# 2017_CARTE_MOFSET.net
KiCad netlist of a schematic drawn in Altium Designer
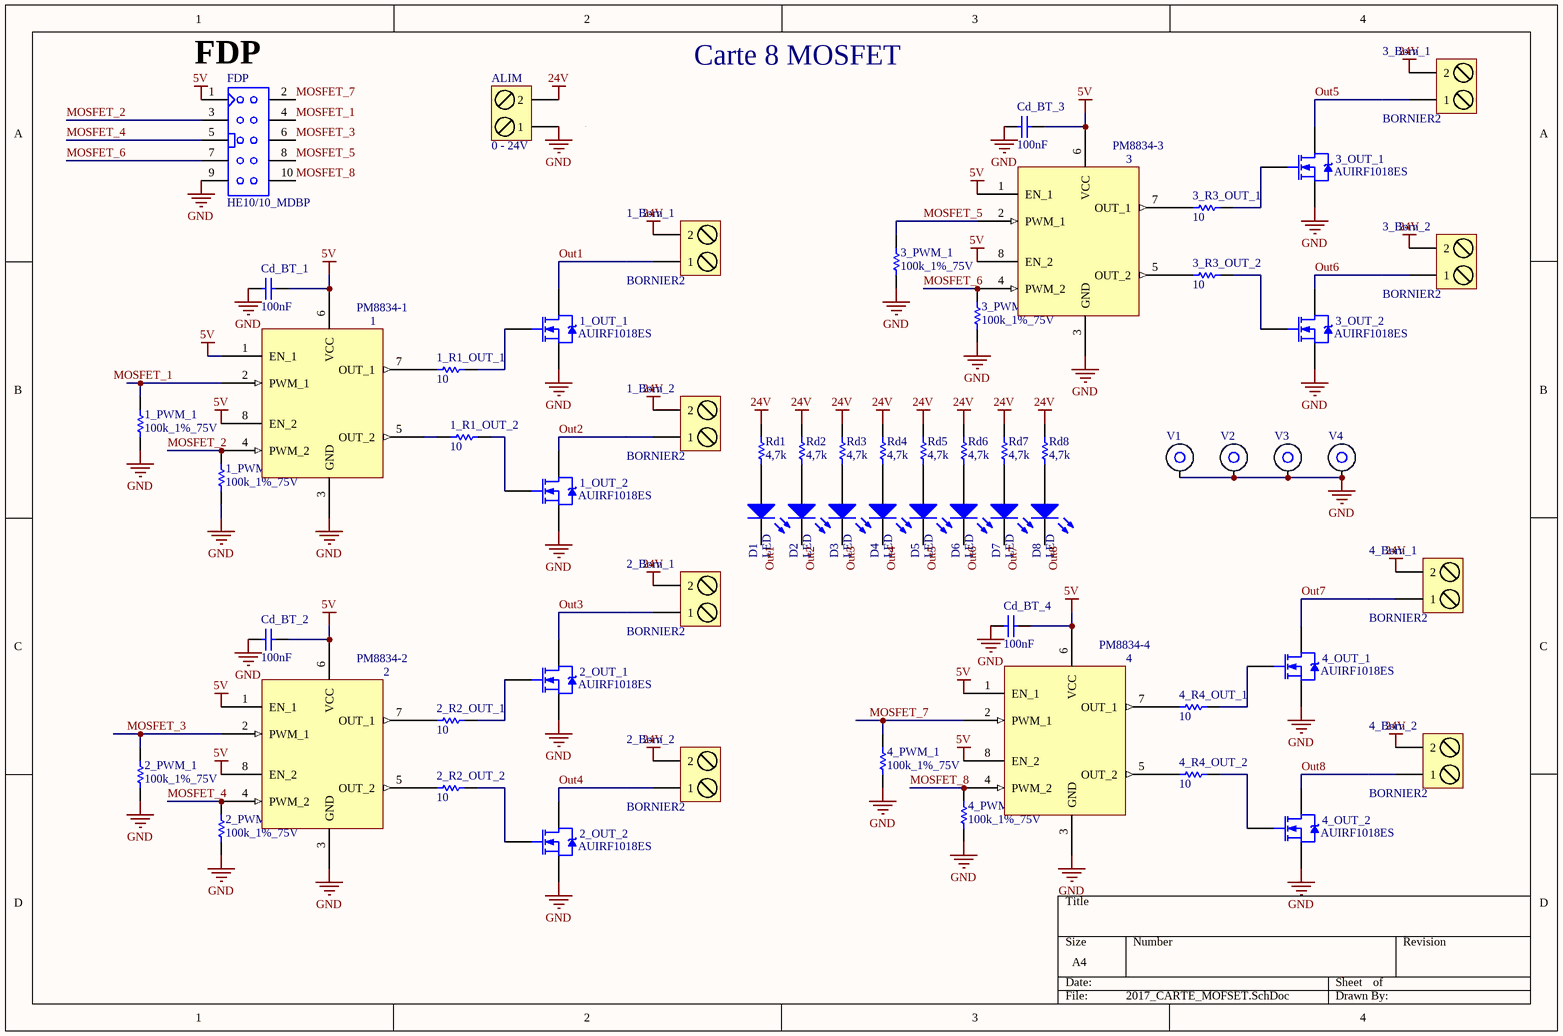
[diagram p0: 2017_CARTE_MOFSET.SchDoc]

(export (version "E")
  (design (tool "Eeschema 10.0.6"))
  (components
    (comp (ref "1")
      (value "PM8834-1")
      (footprint "SO8_N")
      (description "4 A dual low-side MOSFET driver")
      (libsource (lib "_ROBOT") (part "PM8834"))
    )
    (comp (ref "1_Born_1")
      (value "BORNIER2")
      (footprint "BORNIER2")
      (description "Terminal blocks, 2 pins, pitch=5mm")
      (libsource (lib "Connecteur") (part "BORNIER2"))
    )
    (comp (ref "1_Born_2")
      (value "BORNIER2")
      (footprint "BORNIER2")
      (description "Terminal blocks, 2 pins, pitch=5mm")
      (libsource (lib "Connecteur") (part "BORNIER2"))
    )
    (comp (ref "1_OUT_1")
      (value "AUIRF1018ES")
      (footprint "D2PAK_GROS_PAD")
      (description "HEXFET N-Channel Power MOSFET")
      (fields (field (name "PUBLISHER") "Altium Limited"))
      (libsource (lib "IR Discrete MOSFET - Power") (part "IRF1010S"))
    )
    (comp (ref "1_OUT_2")
      (value "AUIRF1018ES")
      (footprint "D2PAK_GROS_PAD")
      (description "HEXFET N-Channel Power MOSFET")
      (fields (field (name "PUBLISHER") "Altium Limited"))
      (libsource (lib "IR Discrete MOSFET - Power") (part "IRF1010S"))
    )
    (comp (ref "1_PWM_1")
      (value "100k_1%_75V")
      (footprint "R1206_N")
      (description "Resistor")
      (fields (field (name "PUBLISHER") "Altium Limited"))
      (libsource (lib "DG_Resistance") (part "Resistor"))
    )
    (comp (ref "1_PWM_2")
      (value "100k_1%_75V")
      (footprint "R1206_N")
      (description "Resistor")
      (fields (field (name "PUBLISHER") "Altium Limited"))
      (libsource (lib "DG_Resistance") (part "Resistor"))
    )
    (comp (ref "1_R1_OUT_1")
      (value "10")
      (footprint "R1206_N")
      (description "Resistor")
      (fields (field (name "PUBLISHER") "Altium Limited"))
      (libsource (lib "_ROBOT") (part "Resistor"))
    )
    (comp (ref "1_R1_OUT_2")
      (value "10")
      (footprint "R1206_N")
      (description "Resistor")
      (fields (field (name "PUBLISHER") "Altium Limited"))
      (libsource (lib "_ROBOT") (part "Resistor"))
    )
    (comp (ref "2")
      (value "PM8834-2")
      (footprint "SO8_N")
      (description "4 A dual low-side MOSFET driver")
      (libsource (lib "_ROBOT") (part "PM8834"))
    )
    (comp (ref "2_Born_1")
      (value "BORNIER2")
      (footprint "BORNIER2")
      (description "Terminal blocks, 2 pins, pitch=5mm")
      (libsource (lib "Connecteur") (part "BORNIER2"))
    )
    (comp (ref "2_Born_2")
      (value "BORNIER2")
      (footprint "BORNIER2")
      (description "Terminal blocks, 2 pins, pitch=5mm")
      (libsource (lib "Connecteur") (part "BORNIER2"))
    )
    (comp (ref "2_OUT_1")
      (value "AUIRF1018ES")
      (footprint "D2PAK_GROS_PAD")
      (description "HEXFET N-Channel Power MOSFET")
      (fields (field (name "PUBLISHER") "Altium Limited"))
      (libsource (lib "IR Discrete MOSFET - Power") (part "IRF1010S"))
    )
    (comp (ref "2_OUT_2")
      (value "AUIRF1018ES")
      (footprint "D2PAK_GROS_PAD")
      (description "HEXFET N-Channel Power MOSFET")
      (fields (field (name "PUBLISHER") "Altium Limited"))
      (libsource (lib "IR Discrete MOSFET - Power") (part "IRF1010S"))
    )
    (comp (ref "2_PWM_1")
      (value "100k_1%_75V")
      (footprint "R1206_N")
      (description "Resistor")
      (fields (field (name "PUBLISHER") "Altium Limited"))
      (libsource (lib "DG_Resistance") (part "Resistor"))
    )
    (comp (ref "2_PWM_2")
      (value "100k_1%_75V")
      (footprint "R1206_N")
      (description "Resistor")
      (fields (field (name "PUBLISHER") "Altium Limited"))
      (libsource (lib "DG_Resistance") (part "Resistor"))
    )
    (comp (ref "2_R2_OUT_1")
      (value "10")
      (footprint "R1206_N")
      (description "Resistor")
      (fields (field (name "PUBLISHER") "Altium Limited"))
      (libsource (lib "_ROBOT") (part "Resistor"))
    )
    (comp (ref "2_R2_OUT_2")
      (value "10")
      (footprint "R1206_N")
      (description "Resistor")
      (fields (field (name "PUBLISHER") "Altium Limited"))
      (libsource (lib "_ROBOT") (part "Resistor"))
    )
    (comp (ref "3")
      (value "PM8834-3")
      (footprint "SO8_N")
      (description "4 A dual low-side MOSFET driver")
      (libsource (lib "_ROBOT") (part "PM8834"))
    )
    (comp (ref "3_Born_1")
      (value "BORNIER2")
      (footprint "BORNIER2")
      (description "Terminal blocks, 2 pins, pitch=5mm")
      (libsource (lib "Connecteur") (part "BORNIER2"))
    )
    (comp (ref "3_Born_2")
      (value "BORNIER2")
      (footprint "BORNIER2")
      (description "Terminal blocks, 2 pins, pitch=5mm")
      (libsource (lib "Connecteur") (part "BORNIER2"))
    )
    (comp (ref "3_OUT_1")
      (value "AUIRF1018ES")
      (footprint "D2PAK_GROS_PAD")
      (description "HEXFET N-Channel Power MOSFET")
      (fields (field (name "PUBLISHER") "Altium Limited"))
      (libsource (lib "IR Discrete MOSFET - Power") (part "IRF1010S"))
    )
    (comp (ref "3_OUT_2")
      (value "AUIRF1018ES")
      (footprint "D2PAK_GROS_PAD")
      (description "HEXFET N-Channel Power MOSFET")
      (fields (field (name "PUBLISHER") "Altium Limited"))
      (libsource (lib "IR Discrete MOSFET - Power") (part "IRF1010S"))
    )
    (comp (ref "3_PWM_1")
      (value "100k_1%_75V")
      (footprint "R1206_N")
      (description "Resistor")
      (fields (field (name "PUBLISHER") "Altium Limited"))
      (libsource (lib "DG_Resistance") (part "Resistor"))
    )
    (comp (ref "3_PWM_2")
      (value "100k_1%_75V")
      (footprint "R1206_N")
      (description "Resistor")
      (fields (field (name "PUBLISHER") "Altium Limited"))
      (libsource (lib "DG_Resistance") (part "Resistor"))
    )
    (comp (ref "3_R3_OUT_1")
      (value "10")
      (footprint "R1206_N")
      (description "Resistor")
      (fields (field (name "PUBLISHER") "Altium Limited"))
      (libsource (lib "_ROBOT") (part "Resistor"))
    )
    (comp (ref "3_R3_OUT_2")
      (value "10")
      (footprint "R1206_N")
      (description "Resistor")
      (fields (field (name "PUBLISHER") "Altium Limited"))
      (libsource (lib "_ROBOT") (part "Resistor"))
    )
    (comp (ref "4")
      (value "PM8834-4")
      (footprint "SO8_N")
      (description "4 A dual low-side MOSFET driver")
      (libsource (lib "_ROBOT") (part "PM8834"))
    )
    (comp (ref "4_Born_1")
      (value "BORNIER2")
      (footprint "BORNIER2")
      (description "Terminal blocks, 2 pins, pitch=5mm")
      (libsource (lib "Connecteur") (part "BORNIER2"))
    )
    (comp (ref "4_Born_2")
      (value "BORNIER2")
      (footprint "BORNIER2")
      (description "Terminal blocks, 2 pins, pitch=5mm")
      (libsource (lib "Connecteur") (part "BORNIER2"))
    )
    (comp (ref "4_OUT_1")
      (value "AUIRF1018ES")
      (footprint "D2PAK_GROS_PAD")
      (description "HEXFET N-Channel Power MOSFET")
      (fields (field (name "PUBLISHER") "Altium Limited"))
      (libsource (lib "IR Discrete MOSFET - Power") (part "IRF1010S"))
    )
    (comp (ref "4_OUT_2")
      (value "AUIRF1018ES")
      (footprint "D2PAK_GROS_PAD")
      (description "HEXFET N-Channel Power MOSFET")
      (fields (field (name "PUBLISHER") "Altium Limited"))
      (libsource (lib "IR Discrete MOSFET - Power") (part "IRF1010S"))
    )
    (comp (ref "4_PWM_1")
      (value "100k_1%_75V")
      (footprint "R1206_N")
      (description "Resistor")
      (fields (field (name "PUBLISHER") "Altium Limited"))
      (libsource (lib "DG_Resistance") (part "Resistor"))
    )
    (comp (ref "4_PWM_2")
      (value "100k_1%_75V")
      (footprint "R1206_N")
      (description "Resistor")
      (fields (field (name "PUBLISHER") "Altium Limited"))
      (libsource (lib "DG_Resistance") (part "Resistor"))
    )
    (comp (ref "4_R4_OUT_1")
      (value "10")
      (footprint "R1206_N")
      (description "Resistor")
      (fields (field (name "PUBLISHER") "Altium Limited"))
      (libsource (lib "_ROBOT") (part "Resistor"))
    )
    (comp (ref "4_R4_OUT_2")
      (value "10")
      (footprint "R1206_N")
      (description "Resistor")
      (fields (field (name "PUBLISHER") "Altium Limited"))
      (libsource (lib "_ROBOT") (part "Resistor"))
    )
    (comp (ref "ALIM")
      (value "0 - 24V")
      (footprint "BORNIER2_FEM_COUDE")
      (description "Terminal blocks, 2 pins, pitch=5mm")
      (libsource (lib "miniprojet") (part "BORNIER2"))
    )
    (comp (ref "Cd_BT_1")
      (value "100nF")
      (footprint "C0805_N")
      (description "Capacitor")
      (fields (field (name "PUBLISHER") "Altium Limited"))
      (libsource (lib "_ROBOT") (part "Condensateur"))
    )
    (comp (ref "Cd_BT_2")
      (value "100nF")
      (footprint "C0805_N")
      (description "Capacitor")
      (fields (field (name "PUBLISHER") "Altium Limited"))
      (libsource (lib "_ROBOT") (part "Condensateur"))
    )
    (comp (ref "Cd_BT_3")
      (value "100nF")
      (footprint "C0805_N")
      (description "Capacitor")
      (fields (field (name "PUBLISHER") "Altium Limited"))
      (libsource (lib "_ROBOT") (part "Condensateur"))
    )
    (comp (ref "Cd_BT_4")
      (value "100nF")
      (footprint "C0805_N")
      (description "Capacitor")
      (fields (field (name "PUBLISHER") "Altium Limited"))
      (libsource (lib "_ROBOT") (part "Condensateur"))
    )
    (comp (ref "D1")
      (value "LED")
      (footprint "LED_0805")
      (description "Typical LED")
      (fields (field (name "PUBLISHER") "Altium Limited"))
      (libsource (lib "_ROBOT") (part "LED"))
    )
    (comp (ref "D2")
      (value "LED")
      (footprint "LED_0805")
      (description "Typical LED")
      (fields (field (name "PUBLISHER") "Altium Limited"))
      (libsource (lib "_ROBOT") (part "LED"))
    )
    (comp (ref "D3")
      (value "LED")
      (footprint "LED_0805")
      (description "Typical LED")
      (fields (field (name "PUBLISHER") "Altium Limited"))
      (libsource (lib "_ROBOT") (part "LED"))
    )
    (comp (ref "D4")
      (value "LED")
      (footprint "LED_0805")
      (description "Typical LED")
      (fields (field (name "PUBLISHER") "Altium Limited"))
      (libsource (lib "_ROBOT") (part "LED"))
    )
    (comp (ref "D5")
      (value "LED")
      (footprint "LED_0805")
      (description "Typical LED")
      (fields (field (name "PUBLISHER") "Altium Limited"))
      (libsource (lib "_ROBOT") (part "LED"))
    )
    (comp (ref "D6")
      (value "LED")
      (footprint "LED_0805")
      (description "Typical LED")
      (fields (field (name "PUBLISHER") "Altium Limited"))
      (libsource (lib "_ROBOT") (part "LED"))
    )
    (comp (ref "D7")
      (value "LED")
      (footprint "LED_0805")
      (description "Typical LED")
      (fields (field (name "PUBLISHER") "Altium Limited"))
      (libsource (lib "_ROBOT") (part "LED"))
    )
    (comp (ref "D8")
      (value "LED")
      (footprint "LED_0805")
      (description "Typical LED")
      (fields (field (name "PUBLISHER") "Altium Limited"))
      (libsource (lib "_ROBOT") (part "LED"))
    )
    (comp (ref "FDP")
      (value "HE10/10_MALE_DROIT_BAS_PROFIL")
      (footprint "HE10/10_M_D_BP")
      (description "EMBASE HE10/10 MALE DROIT BAS PROFIL")
      (fields (field (name "TYPE") "HE10/10_MDBP"))
      (libsource (lib "connecteurs") (part "HE10/10_MALE_DROIT_BAS_PROFIL"))
    )
    (comp (ref "Rd1")
      (value "4,7k")
      (footprint "R1206_N")
      (description "Resistor")
      (fields (field (name "PUBLISHER") "Altium Limited"))
      (libsource (lib "_ROBOT") (part "Resistor"))
    )
    (comp (ref "Rd2")
      (value "4,7k")
      (footprint "R1206_N")
      (description "Resistor")
      (fields (field (name "PUBLISHER") "Altium Limited"))
      (libsource (lib "_ROBOT") (part "Resistor"))
    )
    (comp (ref "Rd3")
      (value "4,7k")
      (footprint "R1206_N")
      (description "Resistor")
      (fields (field (name "PUBLISHER") "Altium Limited"))
      (libsource (lib "_ROBOT") (part "Resistor"))
    )
    (comp (ref "Rd4")
      (value "4,7k")
      (footprint "R1206_N")
      (description "Resistor")
      (fields (field (name "PUBLISHER") "Altium Limited"))
      (libsource (lib "_ROBOT") (part "Resistor"))
    )
    (comp (ref "Rd5")
      (value "4,7k")
      (footprint "R1206_N")
      (description "Resistor")
      (fields (field (name "PUBLISHER") "Altium Limited"))
      (libsource (lib "_ROBOT") (part "Resistor"))
    )
    (comp (ref "Rd6")
      (value "4,7k")
      (footprint "R1206_N")
      (description "Resistor")
      (fields (field (name "PUBLISHER") "Altium Limited"))
      (libsource (lib "_ROBOT") (part "Resistor"))
    )
    (comp (ref "Rd7")
      (value "4,7k")
      (footprint "R1206_N")
      (description "Resistor")
      (fields (field (name "PUBLISHER") "Altium Limited"))
      (libsource (lib "_ROBOT") (part "Resistor"))
    )
    (comp (ref "Rd8")
      (value "4,7k")
      (footprint "R1206_N")
      (description "Resistor")
      (fields (field (name "PUBLISHER") "Altium Limited"))
      (libsource (lib "_ROBOT") (part "Resistor"))
    )
    (comp (ref "V1")
      (value "Entretoise WURTH CMS")
      (footprint "ENTRETOISE_CMS")
      (description "Entretoise Wurth")
      (fields (field (name "PUBLISHER") "Damien Guitton"))
      (libsource (lib "_ROBOT") (part "Entretoise WURTH CMS"))
    )
    (comp (ref "V2")
      (value "Entretoise WURTH CMS")
      (footprint "ENTRETOISE_CMS")
      (description "Entretoise Wurth")
      (fields (field (name "PUBLISHER") "Damien Guitton"))
      (libsource (lib "_ROBOT") (part "Entretoise WURTH CMS"))
    )
    (comp (ref "V3")
      (value "Entretoise WURTH CMS")
      (footprint "ENTRETOISE_CMS")
      (description "Entretoise Wurth")
      (fields (field (name "PUBLISHER") "Damien Guitton"))
      (libsource (lib "_ROBOT") (part "Entretoise WURTH CMS"))
    )
    (comp (ref "V4")
      (value "Entretoise WURTH CMS")
      (footprint "ENTRETOISE_CMS")
      (description "Entretoise Wurth")
      (fields (field (name "PUBLISHER") "Damien Guitton"))
      (libsource (lib "_ROBOT") (part "Entretoise WURTH CMS"))
    )
  )
  (nets
    (net (code "1") (name "/MOSFET_1") (class "Default")
      (node (ref "FDP") (pin "4") (pinfunction "4_4") (pintype "passive"))
    )
    (net (code "2") (name "/MOSFET_2") (class "Default")
      (node (ref "1") (pin "4") (pinfunction "PWM_2_4") (pintype "input"))
      (node (ref "1_PWM_2") (pin "2") (pinfunction "2_2") (pintype "passive"))
      (node (ref "FDP") (pin "3") (pinfunction "3_3") (pintype "passive"))
    )
    (net (code "3") (name "/MOSFET_3") (class "Default")
      (node (ref "2") (pin "2") (pinfunction "PWM_1_2") (pintype "input"))
      (node (ref "2_PWM_1") (pin "2") (pinfunction "2_2") (pintype "passive"))
      (node (ref "FDP") (pin "6") (pinfunction "6_6") (pintype "passive"))
    )
    (net (code "4") (name "/MOSFET_4") (class "Default")
      (node (ref "2") (pin "4") (pinfunction "PWM_2_4") (pintype "input"))
      (node (ref "2_PWM_2") (pin "2") (pinfunction "2_2") (pintype "passive"))
      (node (ref "FDP") (pin "5") (pinfunction "5_5") (pintype "passive"))
    )
    (net (code "5") (name "/MOSFET_5") (class "Default")
      (node (ref "3") (pin "2") (pinfunction "PWM_1_2") (pintype "input"))
      (node (ref "3_PWM_1") (pin "2") (pinfunction "2_2") (pintype "passive"))
      (node (ref "FDP") (pin "8") (pinfunction "8_8") (pintype "passive"))
    )
    (net (code "6") (name "/MOSFET_6") (class "Default")
      (node (ref "3") (pin "4") (pinfunction "PWM_2_4") (pintype "input"))
      (node (ref "3_PWM_2") (pin "2") (pinfunction "2_2") (pintype "passive"))
      (node (ref "FDP") (pin "7") (pinfunction "7_7") (pintype "passive"))
    )
    (net (code "7") (name "/MOSFET_7") (class "Default")
      (node (ref "4") (pin "2") (pinfunction "PWM_1_2") (pintype "input"))
      (node (ref "4_PWM_1") (pin "2") (pinfunction "2_2") (pintype "passive"))
      (node (ref "FDP") (pin "2") (pinfunction "2_2") (pintype "passive"))
    )
    (net (code "8") (name "/MOSFET_8") (class "Default")
      (node (ref "4") (pin "4") (pinfunction "PWM_2_4") (pintype "input"))
      (node (ref "4_PWM_2") (pin "2") (pinfunction "2_2") (pintype "passive"))
      (node (ref "FDP") (pin "10") (pinfunction "10_10") (pintype "passive"))
    )
    (net (code "9") (name "/Out1") (class "Default")
      (node (ref "1_Born_1") (pin "1") (pinfunction "1_1") (pintype "passive"))
      (node (ref "1_OUT_1") (pin "2") (pinfunction "D_2") (pintype "passive"))
      (node (ref "D1") (pin "2") (pinfunction "K_2") (pintype "passive"))
    )
    (net (code "10") (name "/Out2") (class "Default")
      (node (ref "1_Born_2") (pin "1") (pinfunction "1_1") (pintype "passive"))
      (node (ref "1_OUT_2") (pin "2") (pinfunction "D_2") (pintype "passive"))
      (node (ref "D2") (pin "2") (pinfunction "K_2") (pintype "passive"))
    )
    (net (code "11") (name "/Out3") (class "Default")
      (node (ref "2_Born_1") (pin "1") (pinfunction "1_1") (pintype "passive"))
      (node (ref "2_OUT_1") (pin "2") (pinfunction "D_2") (pintype "passive"))
      (node (ref "D3") (pin "2") (pinfunction "K_2") (pintype "passive"))
    )
    (net (code "12") (name "/Out4") (class "Default")
      (node (ref "2_Born_2") (pin "1") (pinfunction "1_1") (pintype "passive"))
      (node (ref "2_OUT_2") (pin "2") (pinfunction "D_2") (pintype "passive"))
      (node (ref "D4") (pin "2") (pinfunction "K_2") (pintype "passive"))
    )
    (net (code "13") (name "/Out5") (class "Default")
      (node (ref "3_Born_1") (pin "1") (pinfunction "1_1") (pintype "passive"))
      (node (ref "3_OUT_1") (pin "2") (pinfunction "D_2") (pintype "passive"))
      (node (ref "D5") (pin "2") (pinfunction "K_2") (pintype "passive"))
    )
    (net (code "14") (name "/Out6") (class "Default")
      (node (ref "3_Born_2") (pin "1") (pinfunction "1_1") (pintype "passive"))
      (node (ref "3_OUT_2") (pin "2") (pinfunction "D_2") (pintype "passive"))
      (node (ref "D6") (pin "2") (pinfunction "K_2") (pintype "passive"))
    )
    (net (code "15") (name "/Out7") (class "Default")
      (node (ref "4_Born_1") (pin "1") (pinfunction "1_1") (pintype "passive"))
      (node (ref "4_OUT_1") (pin "2") (pinfunction "D_2") (pintype "passive"))
      (node (ref "D7") (pin "2") (pinfunction "K_2") (pintype "passive"))
    )
    (net (code "16") (name "/Out8") (class "Default")
      (node (ref "4_Born_2") (pin "1") (pinfunction "1_1") (pintype "passive"))
      (node (ref "4_OUT_2") (pin "2") (pinfunction "D_2") (pintype "passive"))
      (node (ref "D8") (pin "2") (pinfunction "K_2") (pintype "passive"))
    )
    (net (code "17") (name "5V") (class "Default")
      (node (ref "1") (pin "1") (pinfunction "EN_1_1") (pintype "passive"))
      (node (ref "1") (pin "6") (pinfunction "VCC_6") (pintype "power_in"))
      (node (ref "1") (pin "8") (pinfunction "EN_2_8") (pintype "passive"))
      (node (ref "2") (pin "1") (pinfunction "EN_1_1") (pintype "passive"))
      (node (ref "2") (pin "6") (pinfunction "VCC_6") (pintype "power_in"))
      (node (ref "2") (pin "8") (pinfunction "EN_2_8") (pintype "passive"))
      (node (ref "3") (pin "1") (pinfunction "EN_1_1") (pintype "passive"))
      (node (ref "3") (pin "6") (pinfunction "VCC_6") (pintype "power_in"))
      (node (ref "3") (pin "8") (pinfunction "EN_2_8") (pintype "passive"))
      (node (ref "4") (pin "1") (pinfunction "EN_1_1") (pintype "passive"))
      (node (ref "4") (pin "6") (pinfunction "VCC_6") (pintype "power_in"))
      (node (ref "4") (pin "8") (pinfunction "EN_2_8") (pintype "passive"))
      (node (ref "Cd_BT_1") (pin "2") (pinfunction "2_2") (pintype "passive"))
      (node (ref "Cd_BT_2") (pin "2") (pinfunction "2_2") (pintype "passive"))
      (node (ref "Cd_BT_3") (pin "2") (pinfunction "2_2") (pintype "passive"))
      (node (ref "Cd_BT_4") (pin "2") (pinfunction "2_2") (pintype "passive"))
      (node (ref "FDP") (pin "1") (pinfunction "1_1") (pintype "passive"))
    )
    (net (code "18") (name "24V") (class "Default")
      (node (ref "1_Born_1") (pin "2") (pinfunction "2_2") (pintype "passive"))
      (node (ref "1_Born_2") (pin "2") (pinfunction "2_2") (pintype "passive"))
      (node (ref "2_Born_1") (pin "2") (pinfunction "2_2") (pintype "passive"))
      (node (ref "2_Born_2") (pin "2") (pinfunction "2_2") (pintype "passive"))
      (node (ref "3_Born_1") (pin "2") (pinfunction "2_2") (pintype "passive"))
      (node (ref "3_Born_2") (pin "2") (pinfunction "2_2") (pintype "passive"))
      (node (ref "4_Born_1") (pin "2") (pinfunction "2_2") (pintype "passive"))
      (node (ref "4_Born_2") (pin "2") (pinfunction "2_2") (pintype "passive"))
      (node (ref "ALIM") (pin "2") (pinfunction "2_2") (pintype "passive"))
      (node (ref "Rd1") (pin "1") (pinfunction "1_1") (pintype "passive"))
      (node (ref "Rd2") (pin "1") (pinfunction "1_1") (pintype "passive"))
      (node (ref "Rd3") (pin "1") (pinfunction "1_1") (pintype "passive"))
      (node (ref "Rd4") (pin "1") (pinfunction "1_1") (pintype "passive"))
      (node (ref "Rd5") (pin "1") (pinfunction "1_1") (pintype "passive"))
      (node (ref "Rd6") (pin "1") (pinfunction "1_1") (pintype "passive"))
      (node (ref "Rd7") (pin "1") (pinfunction "1_1") (pintype "passive"))
      (node (ref "Rd8") (pin "1") (pinfunction "1_1") (pintype "passive"))
    )
    (net (code "19") (name "GND") (class "Default")
      (node (ref "1") (pin "3") (pinfunction "GND_3") (pintype "power_in"))
      (node (ref "1_OUT_1") (pin "3") (pinfunction "S_3") (pintype "passive"))
      (node (ref "1_OUT_2") (pin "3") (pinfunction "S_3") (pintype "passive"))
      (node (ref "1_PWM_1") (pin "1") (pinfunction "1_1") (pintype "passive"))
      (node (ref "1_PWM_2") (pin "1") (pinfunction "1_1") (pintype "passive"))
      (node (ref "2") (pin "3") (pinfunction "GND_3") (pintype "power_in"))
      (node (ref "2_OUT_1") (pin "3") (pinfunction "S_3") (pintype "passive"))
      (node (ref "2_OUT_2") (pin "3") (pinfunction "S_3") (pintype "passive"))
      (node (ref "2_PWM_1") (pin "1") (pinfunction "1_1") (pintype "passive"))
      (node (ref "2_PWM_2") (pin "1") (pinfunction "1_1") (pintype "passive"))
      (node (ref "3") (pin "3") (pinfunction "GND_3") (pintype "power_in"))
      (node (ref "3_OUT_1") (pin "3") (pinfunction "S_3") (pintype "passive"))
      (node (ref "3_OUT_2") (pin "3") (pinfunction "S_3") (pintype "passive"))
      (node (ref "3_PWM_1") (pin "1") (pinfunction "1_1") (pintype "passive"))
      (node (ref "3_PWM_2") (pin "1") (pinfunction "1_1") (pintype "passive"))
      (node (ref "4") (pin "3") (pinfunction "GND_3") (pintype "power_in"))
      (node (ref "4_OUT_1") (pin "3") (pinfunction "S_3") (pintype "passive"))
      (node (ref "4_OUT_2") (pin "3") (pinfunction "S_3") (pintype "passive"))
      (node (ref "4_PWM_1") (pin "1") (pinfunction "1_1") (pintype "passive"))
      (node (ref "4_PWM_2") (pin "1") (pinfunction "1_1") (pintype "passive"))
      (node (ref "ALIM") (pin "1") (pinfunction "1_1") (pintype "passive"))
      (node (ref "Cd_BT_1") (pin "1") (pinfunction "1_1") (pintype "passive"))
      (node (ref "Cd_BT_2") (pin "1") (pinfunction "1_1") (pintype "passive"))
      (node (ref "Cd_BT_3") (pin "1") (pinfunction "1_1") (pintype "passive"))
      (node (ref "Cd_BT_4") (pin "1") (pinfunction "1_1") (pintype "passive"))
      (node (ref "FDP") (pin "9") (pinfunction "9_9") (pintype "passive"))
      (node (ref "V1") (pin "1") (pinfunction "1_1") (pintype "passive"))
      (node (ref "V2") (pin "1") (pinfunction "1_1") (pintype "passive"))
      (node (ref "V3") (pin "1") (pinfunction "1_1") (pintype "passive"))
      (node (ref "V4") (pin "1") (pinfunction "1_1") (pintype "passive"))
    )
    (net (code "20") (name "Net-(1-OUT_1)") (class "Default")
      (node (ref "1") (pin "7") (pinfunction "OUT_1_7") (pintype "output"))
      (node (ref "1_R1_OUT_1") (pin "1") (pinfunction "1_1") (pintype "passive"))
    )
    (net (code "21") (name "Net-(1-OUT_2)") (class "Default")
      (node (ref "1") (pin "5") (pinfunction "OUT_2_5") (pintype "output"))
      (node (ref "1_R1_OUT_2") (pin "1") (pinfunction "1_1") (pintype "passive"))
    )
    (net (code "22") (name "Net-(1-PWM_1)") (class "Default")
      (node (ref "1") (pin "2") (pinfunction "PWM_1_2") (pintype "input"))
      (node (ref "1_PWM_1") (pin "2") (pinfunction "2_2") (pintype "passive"))
    )
    (net (code "23") (name "Net-(1_OUT_1-G)") (class "Default")
      (node (ref "1_OUT_1") (pin "1") (pinfunction "G_1") (pintype "passive"))
      (node (ref "1_R1_OUT_1") (pin "2") (pinfunction "2_2") (pintype "passive"))
    )
    (net (code "24") (name "Net-(1_OUT_2-G)") (class "Default")
      (node (ref "1_OUT_2") (pin "1") (pinfunction "G_1") (pintype "passive"))
      (node (ref "1_R1_OUT_2") (pin "2") (pinfunction "2_2") (pintype "passive"))
    )
    (net (code "25") (name "Net-(2-OUT_1)") (class "Default")
      (node (ref "2") (pin "7") (pinfunction "OUT_1_7") (pintype "output"))
      (node (ref "2_R2_OUT_1") (pin "1") (pinfunction "1_1") (pintype "passive"))
    )
    (net (code "26") (name "Net-(2-OUT_2)") (class "Default")
      (node (ref "2") (pin "5") (pinfunction "OUT_2_5") (pintype "output"))
      (node (ref "2_R2_OUT_2") (pin "1") (pinfunction "1_1") (pintype "passive"))
    )
    (net (code "27") (name "Net-(2_OUT_1-G)") (class "Default")
      (node (ref "2_OUT_1") (pin "1") (pinfunction "G_1") (pintype "passive"))
      (node (ref "2_R2_OUT_1") (pin "2") (pinfunction "2_2") (pintype "passive"))
    )
    (net (code "28") (name "Net-(2_OUT_2-G)") (class "Default")
      (node (ref "2_OUT_2") (pin "1") (pinfunction "G_1") (pintype "passive"))
      (node (ref "2_R2_OUT_2") (pin "2") (pinfunction "2_2") (pintype "passive"))
    )
    (net (code "29") (name "Net-(3-OUT_1)") (class "Default")
      (node (ref "3") (pin "7") (pinfunction "OUT_1_7") (pintype "output"))
      (node (ref "3_R3_OUT_1") (pin "1") (pinfunction "1_1") (pintype "passive"))
    )
    (net (code "30") (name "Net-(3-OUT_2)") (class "Default")
      (node (ref "3") (pin "5") (pinfunction "OUT_2_5") (pintype "output"))
      (node (ref "3_R3_OUT_2") (pin "1") (pinfunction "1_1") (pintype "passive"))
    )
    (net (code "31") (name "Net-(3_OUT_1-G)") (class "Default")
      (node (ref "3_OUT_1") (pin "1") (pinfunction "G_1") (pintype "passive"))
      (node (ref "3_R3_OUT_1") (pin "2") (pinfunction "2_2") (pintype "passive"))
    )
    (net (code "32") (name "Net-(3_OUT_2-G)") (class "Default")
      (node (ref "3_OUT_2") (pin "1") (pinfunction "G_1") (pintype "passive"))
      (node (ref "3_R3_OUT_2") (pin "2") (pinfunction "2_2") (pintype "passive"))
    )
    (net (code "33") (name "Net-(4-OUT_1)") (class "Default")
      (node (ref "4") (pin "7") (pinfunction "OUT_1_7") (pintype "output"))
      (node (ref "4_R4_OUT_1") (pin "1") (pinfunction "1_1") (pintype "passive"))
    )
    (net (code "34") (name "Net-(4-OUT_2)") (class "Default")
      (node (ref "4") (pin "5") (pinfunction "OUT_2_5") (pintype "output"))
      (node (ref "4_R4_OUT_2") (pin "1") (pinfunction "1_1") (pintype "passive"))
    )
    (net (code "35") (name "Net-(4_OUT_1-G)") (class "Default")
      (node (ref "4_OUT_1") (pin "1") (pinfunction "G_1") (pintype "passive"))
      (node (ref "4_R4_OUT_1") (pin "2") (pinfunction "2_2") (pintype "passive"))
    )
    (net (code "36") (name "Net-(4_OUT_2-G)") (class "Default")
      (node (ref "4_OUT_2") (pin "1") (pinfunction "G_1") (pintype "passive"))
      (node (ref "4_R4_OUT_2") (pin "2") (pinfunction "2_2") (pintype "passive"))
    )
    (net (code "37") (name "Net-(D1-A)") (class "Default")
      (node (ref "D1") (pin "1") (pinfunction "A_1") (pintype "passive"))
      (node (ref "Rd1") (pin "2") (pinfunction "2_2") (pintype "passive"))
    )
    (net (code "38") (name "Net-(D2-A)") (class "Default")
      (node (ref "D2") (pin "1") (pinfunction "A_1") (pintype "passive"))
      (node (ref "Rd2") (pin "2") (pinfunction "2_2") (pintype "passive"))
    )
    (net (code "39") (name "Net-(D3-A)") (class "Default")
      (node (ref "D3") (pin "1") (pinfunction "A_1") (pintype "passive"))
      (node (ref "Rd3") (pin "2") (pinfunction "2_2") (pintype "passive"))
    )
    (net (code "40") (name "Net-(D4-A)") (class "Default")
      (node (ref "D4") (pin "1") (pinfunction "A_1") (pintype "passive"))
      (node (ref "Rd4") (pin "2") (pinfunction "2_2") (pintype "passive"))
    )
    (net (code "41") (name "Net-(D5-A)") (class "Default")
      (node (ref "D5") (pin "1") (pinfunction "A_1") (pintype "passive"))
      (node (ref "Rd5") (pin "2") (pinfunction "2_2") (pintype "passive"))
    )
    (net (code "42") (name "Net-(D6-A)") (class "Default")
      (node (ref "D6") (pin "1") (pinfunction "A_1") (pintype "passive"))
      (node (ref "Rd6") (pin "2") (pinfunction "2_2") (pintype "passive"))
    )
    (net (code "43") (name "Net-(D7-A)") (class "Default")
      (node (ref "D7") (pin "1") (pinfunction "A_1") (pintype "passive"))
      (node (ref "Rd7") (pin "2") (pinfunction "2_2") (pintype "passive"))
    )
    (net (code "44") (name "Net-(D8-A)") (class "Default")
      (node (ref "D8") (pin "1") (pinfunction "A_1") (pintype "passive"))
      (node (ref "Rd8") (pin "2") (pinfunction "2_2") (pintype "passive"))
    )
  )
)
